# as14120_x31_adc.net
KiCad netlist of a schematic drawn in Altium Designer
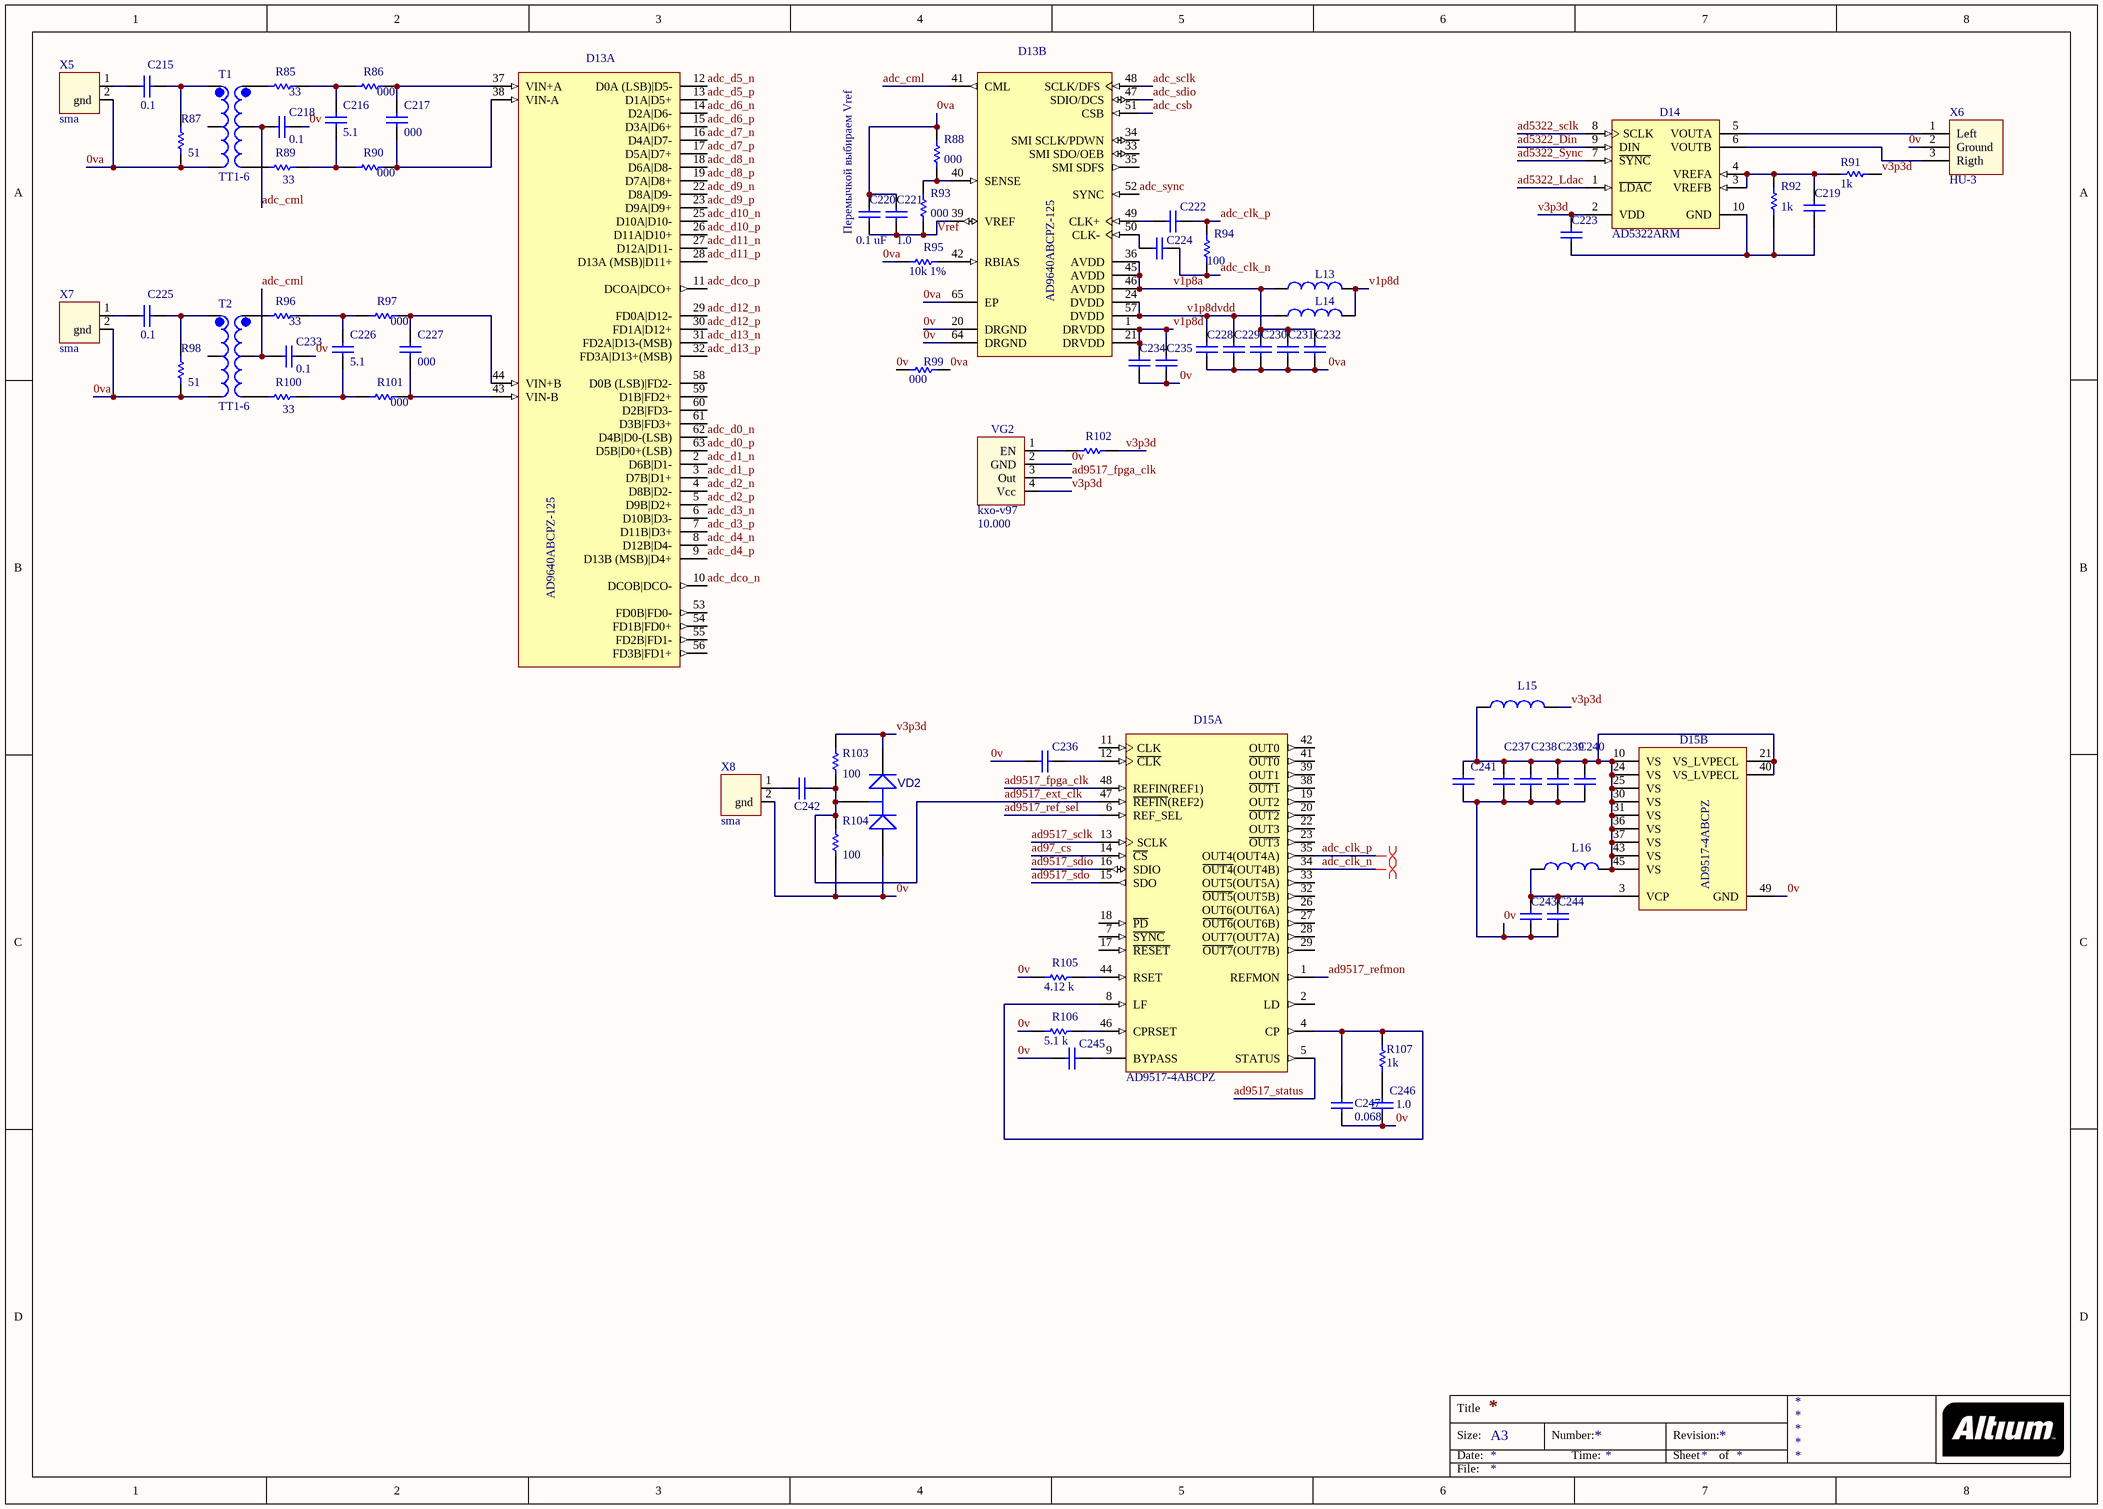
[diagram p0: as14120_x31_adc.SchDoc]

(export (version "E")
  (design (tool "Eeschema 10.0.6"))
  (components
    (comp (ref "C215")
      (value "0.1")
      (footprint "CAPC0402(1005)60_M")
      (description "CAP 1uF 10V ±20% 0402 (1005 Metric) Thickness 0.6mm SMD")
      (fields (field (name "TOLERANCE") "±20%") (field (name "Comment") "CAP 1uF 10V 0402(1005)"))
      (libsource (lib "as14120") (part "CAP_0402"))
    )
    (comp (ref "C216")
      (value "5.1")
      (footprint "CAPC0805(2012)100_N")
      (fields (field (name "Comment") "CAP_0805"))
      (libsource (lib "as14120") (part "CAP_0805"))
    )
    (comp (ref "C217")
      (value "000")
      (footprint "CAPC0805(2012)100_N")
      (fields (field (name "Comment") "CAP_0805"))
      (libsource (lib "as14120") (part "CAP_0805"))
    )
    (comp (ref "C218")
      (value "0.1")
      (footprint "CAPC0402(1005)60_M")
      (description "CAP 1uF 10V ±20% 0402 (1005 Metric) Thickness 0.6mm SMD")
      (fields (field (name "TOLERANCE") "±20%") (field (name "Comment") "CAP 1uF 10V 0402(1005)"))
      (libsource (lib "as14120") (part "CAP_0402"))
    )
    (comp (ref "C219")
      (value "CAP 1uF 10V 0402(1005)")
      (footprint "CAPC0402(1005)60_M")
      (description "CAP 1uF 10V ±20% 0402 (1005 Metric) Thickness 0.6mm SMD")
      (fields (field (name "TOLERANCE") "±20%"))
      (libsource (lib "as14120") (part "CAP_0402"))
    )
    (comp (ref "C220")
      (value "0.1 uF")
      (footprint "CAPC0402(1005)60_M")
      (description "CAP 1uF 10V ±20% 0402 (1005 Metric) Thickness 0.6mm SMD")
      (fields (field (name "TOLERANCE") "±20%") (field (name "Comment") "CAP 1uF 10V 0402(1005)"))
      (libsource (lib "as14120") (part "CAP_0402"))
    )
    (comp (ref "C221")
      (value "1.0")
      (footprint "CAPC0402(1005)60_M")
      (description "CAP 1uF 10V ±20% 0402 (1005 Metric) Thickness 0.6mm SMD")
      (fields (field (name "TOLERANCE") "±20%") (field (name "Comment") "CAP 1uF 10V 0402(1005)"))
      (libsource (lib "as14120") (part "CAP_0402"))
    )
    (comp (ref "C222")
      (value "CAP 1uF 10V 0402(1005)")
      (footprint "CAPC0402(1005)60_M")
      (description "CAP 1uF 10V ±20% 0402 (1005 Metric) Thickness 0.6mm SMD")
      (fields (field (name "TOLERANCE") "±20%"))
      (libsource (lib "as14120") (part "CAP_0402"))
    )
    (comp (ref "C223")
      (value "CAP 1uF 10V 0402(1005)")
      (footprint "CAPC0402(1005)60_M")
      (description "CAP 1uF 10V ±20% 0402 (1005 Metric) Thickness 0.6mm SMD")
      (fields (field (name "TOLERANCE") "±20%"))
      (libsource (lib "as14120") (part "CAP_0402"))
    )
    (comp (ref "C224")
      (value "CAP 1uF 10V 0402(1005)")
      (footprint "CAPC0402(1005)60_M")
      (description "CAP 1uF 10V ±20% 0402 (1005 Metric) Thickness 0.6mm SMD")
      (fields (field (name "TOLERANCE") "±20%"))
      (libsource (lib "as14120") (part "CAP_0402"))
    )
    (comp (ref "C225")
      (value "0.1")
      (footprint "CAPC0402(1005)60_M")
      (description "CAP 1uF 10V ±20% 0402 (1005 Metric) Thickness 0.6mm SMD")
      (fields (field (name "TOLERANCE") "±20%") (field (name "Comment") "CAP 1uF 10V 0402(1005)"))
      (libsource (lib "as14120") (part "CAP_0402"))
    )
    (comp (ref "C226")
      (value "5.1")
      (footprint "CAPC0805(2012)100_N")
      (fields (field (name "Comment") "CAP_0805"))
      (libsource (lib "as14120") (part "CAP_0805"))
    )
    (comp (ref "C227")
      (value "000")
      (footprint "CAPC0805(2012)100_N")
      (fields (field (name "Comment") "CAP_0805"))
      (libsource (lib "as14120") (part "CAP_0805"))
    )
    (comp (ref "C228")
      (value "CAP 1uF 10V 0402(1005)")
      (footprint "CAPC0402(1005)60_M")
      (description "CAP 1uF 10V ±20% 0402 (1005 Metric) Thickness 0.6mm SMD")
      (fields (field (name "TOLERANCE") "±20%"))
      (libsource (lib "as14120") (part "CAP_0402"))
    )
    (comp (ref "C229")
      (value "CAP 1uF 10V 0402(1005)")
      (footprint "CAPC0402(1005)60_M")
      (description "CAP 1uF 10V ±20% 0402 (1005 Metric) Thickness 0.6mm SMD")
      (fields (field (name "TOLERANCE") "±20%"))
      (libsource (lib "as14120") (part "CAP_0402"))
    )
    (comp (ref "C230")
      (value "CAP 1uF 10V 0402(1005)")
      (footprint "CAPC0402(1005)60_M")
      (description "CAP 1uF 10V ±20% 0402 (1005 Metric) Thickness 0.6mm SMD")
      (fields (field (name "TOLERANCE") "±20%"))
      (libsource (lib "as14120") (part "CAP_0402"))
    )
    (comp (ref "C231")
      (value "CAP 1uF 10V 0402(1005)")
      (footprint "CAPC0402(1005)60_M")
      (description "CAP 1uF 10V ±20% 0402 (1005 Metric) Thickness 0.6mm SMD")
      (fields (field (name "TOLERANCE") "±20%"))
      (libsource (lib "as14120") (part "CAP_0402"))
    )
    (comp (ref "C232")
      (value "CAP 1uF 10V 0402(1005)")
      (footprint "CAPC0402(1005)60_M")
      (description "CAP 1uF 10V ±20% 0402 (1005 Metric) Thickness 0.6mm SMD")
      (fields (field (name "TOLERANCE") "±20%"))
      (libsource (lib "as14120") (part "CAP_0402"))
    )
    (comp (ref "C233")
      (value "0.1")
      (footprint "CAPC0402(1005)60_M")
      (description "CAP 1uF 10V ±20% 0402 (1005 Metric) Thickness 0.6mm SMD")
      (fields (field (name "TOLERANCE") "±20%") (field (name "Comment") "CAP 1uF 10V 0402(1005)"))
      (libsource (lib "as14120") (part "CAP_0402"))
    )
    (comp (ref "C234")
      (value "CAP 1uF 10V 0402(1005)")
      (footprint "CAPC0402(1005)60_M")
      (description "CAP 1uF 10V ±20% 0402 (1005 Metric) Thickness 0.6mm SMD")
      (fields (field (name "TOLERANCE") "±20%"))
      (libsource (lib "as14120") (part "CAP_0402"))
    )
    (comp (ref "C235")
      (value "CAP 1uF 10V 0402(1005)")
      (footprint "CAPC0402(1005)60_M")
      (description "CAP 1uF 10V ±20% 0402 (1005 Metric) Thickness 0.6mm SMD")
      (fields (field (name "TOLERANCE") "±20%"))
      (libsource (lib "as14120") (part "CAP_0402"))
    )
    (comp (ref "C236")
      (value "CAP 1uF 10V 0402(1005)")
      (footprint "CAPC0402(1005)60_M")
      (description "CAP 1uF 10V ±20% 0402 (1005 Metric) Thickness 0.6mm SMD")
      (fields (field (name "TOLERANCE") "±20%"))
      (libsource (lib "as14120") (part "CAP_0402"))
    )
    (comp (ref "C237")
      (value "CAP 1uF 10V 0402(1005)")
      (footprint "CAPC0402(1005)60_M")
      (description "CAP 1uF 10V ±20% 0402 (1005 Metric) Thickness 0.6mm SMD")
      (fields (field (name "TOLERANCE") "±20%"))
      (libsource (lib "as14120") (part "CAP_0402"))
    )
    (comp (ref "C238")
      (value "CAP 1uF 10V 0402(1005)")
      (footprint "CAPC0402(1005)60_M")
      (description "CAP 1uF 10V ±20% 0402 (1005 Metric) Thickness 0.6mm SMD")
      (fields (field (name "TOLERANCE") "±20%"))
      (libsource (lib "as14120") (part "CAP_0402"))
    )
    (comp (ref "C239")
      (value "CAP 1uF 10V 0402(1005)")
      (footprint "CAPC0402(1005)60_M")
      (description "CAP 1uF 10V ±20% 0402 (1005 Metric) Thickness 0.6mm SMD")
      (fields (field (name "TOLERANCE") "±20%"))
      (libsource (lib "as14120") (part "CAP_0402"))
    )
    (comp (ref "C240")
      (value "CAP 1uF 10V 0402(1005)")
      (footprint "CAPC0402(1005)60_M")
      (description "CAP 1uF 10V ±20% 0402 (1005 Metric) Thickness 0.6mm SMD")
      (fields (field (name "TOLERANCE") "±20%"))
      (libsource (lib "as14120") (part "CAP_0402"))
    )
    (comp (ref "C241")
      (value "CAP 1uF 10V 0402(1005)")
      (footprint "CAPC0402(1005)60_M")
      (description "CAP 1uF 10V ±20% 0402 (1005 Metric) Thickness 0.6mm SMD")
      (fields (field (name "TOLERANCE") "±20%"))
      (libsource (lib "as14120") (part "CAP_0402"))
    )
    (comp (ref "C242")
      (value "CAP 1uF 10V 0402(1005)")
      (footprint "CAPC0402(1005)60_M")
      (description "CAP 1uF 10V ±20% 0402 (1005 Metric) Thickness 0.6mm SMD")
      (fields (field (name "TOLERANCE") "±20%"))
      (libsource (lib "as14120") (part "CAP_0402"))
    )
    (comp (ref "C243")
      (value "CAP 1uF 10V 0402(1005)")
      (footprint "CAPC0402(1005)60_M")
      (description "CAP 1uF 10V ±20% 0402 (1005 Metric) Thickness 0.6mm SMD")
      (fields (field (name "TOLERANCE") "±20%"))
      (libsource (lib "as14120") (part "CAP_0402"))
    )
    (comp (ref "C244")
      (value "CAP 1uF 10V 0402(1005)")
      (footprint "CAPC0402(1005)60_M")
      (description "CAP 1uF 10V ±20% 0402 (1005 Metric) Thickness 0.6mm SMD")
      (fields (field (name "TOLERANCE") "±20%"))
      (libsource (lib "as14120") (part "CAP_0402"))
    )
    (comp (ref "C245")
      (value "CAP 1uF 10V 0402(1005)")
      (footprint "CAPC0402(1005)60_M")
      (description "CAP 1uF 10V ±20% 0402 (1005 Metric) Thickness 0.6mm SMD")
      (fields (field (name "TOLERANCE") "±20%"))
      (libsource (lib "as14120") (part "CAP_0402"))
    )
    (comp (ref "C246")
      (value "1.0")
      (footprint "CAPC0805(2012)100_N")
      (fields (field (name "Comment") "CAP_0805"))
      (libsource (lib "as14120") (part "CAP_0805"))
    )
    (comp (ref "C247")
      (value "0.068")
      (footprint "CAPC0805(2012)100_N")
      (fields (field (name "Comment") "CAP_0805"))
      (libsource (lib "as14120") (part "CAP_0805"))
    )
    (comp (ref "D13")
      (value "AD9640ABCPZ-125")
      (footprint "CP-64-6_N")
      (fields (field (name "PART NUMBER") "AD9640-125") (field (name "MANUFACTURER") "Analog Devices"))
      (libsource (lib "Analog Devices Data Converters Analog-to-Digital Converters") (part "AD9640ABCPZ-125"))
    )
    (comp (ref "D14")
      (value "AD5322ARM")
      (footprint "RM-10_L")
      (fields (field (name "ADI PART NUMBER") "AD5322") (field (name "MANUFACTURER") "Analog Devices"))
      (libsource (lib "Analog Devices Data Converters Digital-to-Analog Converters") (part "AD5322ARM"))
    )
    (comp (ref "D15")
      (value "AD9517-4ABCPZ")
      (footprint "ADI-CP-48-8_L")
      (libsource (lib "Analog Devices RF IF Timing ICs and Clocks") (part "AD9517-4ABCPZ"))
    )
    (comp (ref "L13")
      (value "BLM21PG300SN1D")
      (footprint "CAPC0805(2012)100_N")
      (libsource (lib "as14120") (part "Ferrite_beat"))
    )
    (comp (ref "L14")
      (value "BLM21PG300SN1D")
      (footprint "CAPC0805(2012)100_N")
      (libsource (lib "as14120") (part "Ferrite_beat"))
    )
    (comp (ref "L15")
      (value "BLM21PG300SN1D")
      (footprint "CAPC0805(2012)100_N")
      (libsource (lib "as14120") (part "Ferrite_beat"))
    )
    (comp (ref "L16")
      (value "BLM21PG300SN1D")
      (footprint "CAPC0805(2012)100_N")
      (libsource (lib "as14120") (part "Ferrite_beat"))
    )
    (comp (ref "R85")
      (value "33")
      (footprint "RESC0805(2012)_L")
      (description "1K 0.125W 1% 0805 (2012 Metric)  SMD")
      (fields (field (name "TOLERANCE") "1 %") (field (name "POWER") "0.125 W"))
      (libsource (lib "as14120") (part "RES_0805"))
    )
    (comp (ref "R86")
      (value "000")
      (footprint "RESC0805(2012)_L")
      (description "1K 0.125W 1% 0805 (2012 Metric)  SMD")
      (fields (field (name "TOLERANCE") "1 %") (field (name "POWER") "0.125 W"))
      (libsource (lib "as14120") (part "RES_0805"))
    )
    (comp (ref "R87")
      (value "51")
      (footprint "RESC0805(2012)_L")
      (description "1K 0.125W 1% 0805 (2012 Metric)  SMD")
      (fields (field (name "TOLERANCE") "1 %") (field (name "POWER") "0.125 W"))
      (libsource (lib "as14120") (part "RES_0805"))
    )
    (comp (ref "R88")
      (value "000")
      (footprint "RESC0603(1608)_L")
      (description "1K 0.1W 5% 0603 (1608 Metric)  SMD")
      (fields (field (name "TOLERANCE") "5 %") (field (name "POWER") "0.1 W"))
      (libsource (lib "as14120") (part "RES_0603"))
    )
    (comp (ref "R89")
      (value "33")
      (footprint "RESC0805(2012)_L")
      (description "1K 0.125W 1% 0805 (2012 Metric)  SMD")
      (fields (field (name "TOLERANCE") "1 %") (field (name "POWER") "0.125 W"))
      (libsource (lib "as14120") (part "RES_0805"))
    )
    (comp (ref "R90")
      (value "000")
      (footprint "RESC0805(2012)_L")
      (description "1K 0.125W 1% 0805 (2012 Metric)  SMD")
      (fields (field (name "TOLERANCE") "1 %") (field (name "POWER") "0.125 W"))
      (libsource (lib "as14120") (part "RES_0805"))
    )
    (comp (ref "R91")
      (value "1k")
      (footprint "RESC0603(1608)_L")
      (description "1K 0.1W 5% 0603 (1608 Metric)  SMD")
      (fields (field (name "TOLERANCE") "5 %") (field (name "POWER") "0.1 W"))
      (libsource (lib "as14120") (part "RES_0603"))
    )
    (comp (ref "R92")
      (value "1k")
      (footprint "RESC0603(1608)_L")
      (description "1K 0.1W 5% 0603 (1608 Metric)  SMD")
      (fields (field (name "TOLERANCE") "5 %") (field (name "POWER") "0.1 W"))
      (libsource (lib "as14120") (part "RES_0603"))
    )
    (comp (ref "R93")
      (value "000")
      (footprint "RESC0603(1608)_L")
      (description "1K 0.1W 5% 0603 (1608 Metric)  SMD")
      (fields (field (name "TOLERANCE") "5 %") (field (name "POWER") "0.1 W"))
      (libsource (lib "as14120") (part "RES_0603"))
    )
    (comp (ref "R94")
      (value "100")
      (footprint "RESC0805(2012)_L")
      (description "1K 0.125W 1% 0805 (2012 Metric)  SMD")
      (fields (field (name "TOLERANCE") "1 %") (field (name "POWER") "0.125 W"))
      (libsource (lib "as14120") (part "RES_0805"))
    )
    (comp (ref "R95")
      (value "10k 1%")
      (footprint "RESC0805(2012)_L")
      (description "1K 0.125W 1% 0805 (2012 Metric)  SMD")
      (fields (field (name "TOLERANCE") "1 %") (field (name "POWER") "0.125 W"))
      (libsource (lib "as14120") (part "RES_0805"))
    )
    (comp (ref "R96")
      (value "33")
      (footprint "RESC0805(2012)_L")
      (description "1K 0.125W 1% 0805 (2012 Metric)  SMD")
      (fields (field (name "TOLERANCE") "1 %") (field (name "POWER") "0.125 W"))
      (libsource (lib "as14120") (part "RES_0805"))
    )
    (comp (ref "R97")
      (value "000")
      (footprint "RESC0805(2012)_L")
      (description "1K 0.125W 1% 0805 (2012 Metric)  SMD")
      (fields (field (name "TOLERANCE") "1 %") (field (name "POWER") "0.125 W"))
      (libsource (lib "as14120") (part "RES_0805"))
    )
    (comp (ref "R98")
      (value "51")
      (footprint "RESC0805(2012)_L")
      (description "1K 0.125W 1% 0805 (2012 Metric)  SMD")
      (fields (field (name "TOLERANCE") "1 %") (field (name "POWER") "0.125 W"))
      (libsource (lib "as14120") (part "RES_0805"))
    )
    (comp (ref "R99")
      (value "000")
      (footprint "RESC0603(1608)_L")
      (description "1K 0.1W 5% 0603 (1608 Metric)  SMD")
      (fields (field (name "TOLERANCE") "5 %") (field (name "POWER") "0.1 W"))
      (libsource (lib "as14120") (part "RES_0603"))
    )
    (comp (ref "R100")
      (value "33")
      (footprint "RESC0805(2012)_L")
      (description "1K 0.125W 1% 0805 (2012 Metric)  SMD")
      (fields (field (name "TOLERANCE") "1 %") (field (name "POWER") "0.125 W"))
      (libsource (lib "as14120") (part "RES_0805"))
    )
    (comp (ref "R101")
      (value "000")
      (footprint "RESC0805(2012)_L")
      (description "1K 0.125W 1% 0805 (2012 Metric)  SMD")
      (fields (field (name "TOLERANCE") "1 %") (field (name "POWER") "0.125 W"))
      (libsource (lib "as14120") (part "RES_0805"))
    )
    (comp (ref "R102")
      (value "1K 5% 0603(1608)")
      (footprint "RESC0603(1608)_L")
      (description "1K 0.1W 5% 0603 (1608 Metric)  SMD")
      (fields (field (name "TOLERANCE") "5 %") (field (name "POWER") "0.1 W"))
      (libsource (lib "as14120") (part "RES_0603"))
    )
    (comp (ref "R103")
      (value "100")
      (footprint "RESC0805(2012)_L")
      (description "1K 0.125W 1% 0805 (2012 Metric)  SMD")
      (fields (field (name "TOLERANCE") "1 %") (field (name "POWER") "0.125 W"))
      (libsource (lib "as14120") (part "RES_0805"))
    )
    (comp (ref "R104")
      (value "100")
      (footprint "RESC0805(2012)_L")
      (description "1K 0.125W 1% 0805 (2012 Metric)  SMD")
      (fields (field (name "TOLERANCE") "1 %") (field (name "POWER") "0.125 W"))
      (libsource (lib "as14120") (part "RES_0805"))
    )
    (comp (ref "R105")
      (value "4.12 k")
      (footprint "RESC0805(2012)_L")
      (description "1K 0.125W 1% 0805 (2012 Metric)  SMD")
      (fields (field (name "TOLERANCE") "1 %") (field (name "POWER") "0.125 W"))
      (libsource (lib "as14120") (part "RES_0805"))
    )
    (comp (ref "R106")
      (value "5.1 k")
      (footprint "RESC0805(2012)_L")
      (description "1K 0.125W 1% 0805 (2012 Metric)  SMD")
      (fields (field (name "TOLERANCE") "1 %") (field (name "POWER") "0.125 W"))
      (libsource (lib "as14120") (part "RES_0805"))
    )
    (comp (ref "R107")
      (value "1k")
      (footprint "RESC0805(2012)_L")
      (description "1K 0.125W 1% 0805 (2012 Metric)  SMD")
      (fields (field (name "TOLERANCE") "1 %") (field (name "POWER") "0.125 W"))
      (libsource (lib "as14120") (part "RES_0805"))
    )
    (comp (ref "T1") (value "TT1-6") (footprint "TT!-6-KK81") (libsource (lib "as14120") (part "TT1-6-KK81")))
    (comp (ref "T2") (value "TT1-6") (footprint "TT!-6-KK81") (libsource (lib "as14120") (part "TT1-6-KK81")))
    (comp (ref "VD2")
      (value "BAV99")
      (footprint "SO-G3/X.9")
      (description "SOT23 Silicon Planar High-Speed Switching Series Diode Pair")
      (libsource (lib "alexsb") (part "BAV99"))
    )
    (comp (ref "VG2")
      (value "kxo-v97")
      (footprint "kxo-v97")
      (fields (field (name "ALTIUM_VALUE") "10.000"))
      (libsource (lib "as14120") (part "kxo-v97"))
    )
    (comp (ref "X5") (value "sma") (footprint "sma") (libsource (lib "as14120") (part "sma")))
    (comp (ref "X6") (value "HU-3") (footprint "HU-3") (libsource (lib "as14120") (part "HU-3")))
    (comp (ref "X7") (value "sma") (footprint "sma") (libsource (lib "as14120") (part "sma")))
    (comp (ref "X8") (value "sma") (footprint "sma") (libsource (lib "as14120") (part "sma")))
  )
  (nets
    (net (code "1") (name "/0v") (class "Default")
      (node (ref "C218") (pin "2") (pinfunction "2_2") (pintype "passive"))
      (node (ref "C233") (pin "2") (pinfunction "2_2") (pintype "passive"))
      (node (ref "C234") (pin "1") (pinfunction "1_1") (pintype "passive"))
      (node (ref "C235") (pin "1") (pinfunction "1_1") (pintype "passive"))
      (node (ref "C236") (pin "1") (pinfunction "1_1") (pintype "passive"))
      (node (ref "C237") (pin "1") (pinfunction "1_1") (pintype "passive"))
      (node (ref "C238") (pin "1") (pinfunction "1_1") (pintype "passive"))
      (node (ref "C239") (pin "1") (pinfunction "1_1") (pintype "passive"))
      (node (ref "C240") (pin "1") (pinfunction "1_1") (pintype "passive"))
      (node (ref "C241") (pin "1") (pinfunction "1_1") (pintype "passive"))
      (node (ref "C243") (pin "1") (pinfunction "1_1") (pintype "passive"))
      (node (ref "C244") (pin "1") (pinfunction "1_1") (pintype "passive"))
      (node (ref "C245") (pin "1") (pinfunction "1_1") (pintype "passive"))
      (node (ref "C246") (pin "1") (pinfunction "1_1") (pintype "passive"))
      (node (ref "C247") (pin "1") (pinfunction "1_1") (pintype "passive"))
      (node (ref "D13") (pin "20") (pinfunction "DRGND_20") (pintype "power_in"))
      (node (ref "D13") (pin "64") (pinfunction "DRGND_64") (pintype "power_in"))
      (node (ref "D15") (pin "49") (pinfunction "GND_49") (pintype "power_in"))
      (node (ref "R104") (pin "1") (pinfunction "1_1") (pintype "passive"))
      (node (ref "R105") (pin "2") (pinfunction "2_2") (pintype "passive"))
      (node (ref "R106") (pin "2") (pinfunction "2_2") (pintype "passive"))
      (node (ref "R99") (pin "1") (pinfunction "1_1") (pintype "passive"))
      (node (ref "VD2") (pin "3") (pinfunction "A_3") (pintype "passive"))
      (node (ref "VG2") (pin "2") (pinfunction "GND_2") (pintype "passive"))
      (node (ref "X6") (pin "2") (pinfunction "Ground_2") (pintype "passive"))
      (node (ref "X8") (pin "2") (pinfunction "gnd_2") (pintype "passive"))
    )
    (net (code "2") (name "/0va") (class "Default")
      (node (ref "C220") (pin "2") (pinfunction "2_2") (pintype "passive"))
      (node (ref "C221") (pin "2") (pinfunction "2_2") (pintype "passive"))
      (node (ref "C228") (pin "1") (pinfunction "1_1") (pintype "passive"))
      (node (ref "C229") (pin "1") (pinfunction "1_1") (pintype "passive"))
      (node (ref "C230") (pin "1") (pinfunction "1_1") (pintype "passive"))
      (node (ref "C231") (pin "1") (pinfunction "1_1") (pintype "passive"))
      (node (ref "C232") (pin "1") (pinfunction "1_1") (pintype "passive"))
      (node (ref "D13") (pin "65") (pinfunction "EP_65") (pintype "power_in"))
      (node (ref "R87") (pin "1") (pinfunction "1_1") (pintype "passive"))
      (node (ref "R88") (pin "1") (pinfunction "1_1") (pintype "passive"))
      (node (ref "R95") (pin "2") (pinfunction "2_2") (pintype "passive"))
      (node (ref "R98") (pin "1") (pinfunction "1_1") (pintype "passive"))
      (node (ref "R99") (pin "2") (pinfunction "2_2") (pintype "passive"))
      (node (ref "T1") (pin "6") (pinfunction "6_6") (pintype "passive"))
      (node (ref "T2") (pin "6") (pinfunction "6_6") (pintype "passive"))
      (node (ref "X5") (pin "2") (pinfunction "gnd_2") (pintype "passive"))
      (node (ref "X7") (pin "2") (pinfunction "gnd_2") (pintype "passive"))
    )
    (net (code "3") (name "/Vref") (class "Default")
      (node (ref "C220") (pin "1") (pinfunction "1_1") (pintype "passive"))
      (node (ref "C221") (pin "1") (pinfunction "1_1") (pintype "passive"))
      (node (ref "D13") (pin "39") (pinfunction "VREF_39") (pintype "bidirectional"))
      (node (ref "R93") (pin "2") (pinfunction "2_2") (pintype "passive"))
    )
    (net (code "4") (name "/ad97_cs") (class "Default")
      (node (ref "D15") (pin "14") (pinfunction "~{CS}_14") (pintype "input"))
    )
    (net (code "5") (name "/ad5322_Din") (class "Default")
      (node (ref "D14") (pin "9") (pinfunction "DIN_9") (pintype "input"))
    )
    (net (code "6") (name "/ad5322_Ldac") (class "Default")
      (node (ref "D14") (pin "1") (pinfunction "~{LDAC}_1") (pintype "input"))
    )
    (net (code "7") (name "/ad5322_Sync") (class "Default")
      (node (ref "D14") (pin "7") (pinfunction "~{SYNC}_7") (pintype "input"))
    )
    (net (code "8") (name "/ad5322_sclk") (class "Default")
      (node (ref "D14") (pin "8") (pinfunction "SCLK_8") (pintype "input"))
    )
    (net (code "9") (name "/ad9517_ext_clk") (class "Default")
      (node (ref "C242") (pin "2") (pinfunction "2_2") (pintype "passive"))
      (node (ref "D15") (pin "47") (pinfunction "~{REFIN}(REF2)_47") (pintype "input"))
      (node (ref "R103") (pin "1") (pinfunction "1_1") (pintype "passive"))
      (node (ref "R104") (pin "2") (pinfunction "2_2") (pintype "passive"))
      (node (ref "VD2") (pin "1") (pinfunction "C_1") (pintype "passive"))
    )
    (net (code "10") (name "/ad9517_fpga_clk") (class "Default")
      (node (ref "D15") (pin "48") (pinfunction "REFIN(REF1)_48") (pintype "input"))
      (node (ref "VG2") (pin "3") (pinfunction "Out_3") (pintype "passive"))
    )
    (net (code "11") (name "/ad9517_ref_sel") (class "Default")
      (node (ref "D15") (pin "6") (pinfunction "REF_SEL_6") (pintype "input"))
    )
    (net (code "12") (name "/ad9517_refmon") (class "Default")
      (node (ref "D15") (pin "1") (pinfunction "REFMON_1") (pintype "output"))
    )
    (net (code "13") (name "/ad9517_sclk") (class "Default")
      (node (ref "D15") (pin "13") (pinfunction "SCLK_13") (pintype "input"))
    )
    (net (code "14") (name "/ad9517_sdio") (class "Default")
      (node (ref "D15") (pin "16") (pinfunction "SDIO_16") (pintype "bidirectional"))
    )
    (net (code "15") (name "/ad9517_sdo") (class "Default")
      (node (ref "D15") (pin "15") (pinfunction "SDO_15") (pintype "output"))
    )
    (net (code "16") (name "/ad9517_status") (class "Default")
      (node (ref "D15") (pin "5") (pinfunction "STATUS_5") (pintype "output"))
    )
    (net (code "17") (name "/adc_clk_n") (class "Default")
      (node (ref "C224") (pin "1") (pinfunction "1_1") (pintype "passive"))
      (node (ref "D15") (pin "34") (pinfunction "~{OUT4}(OUT4B)_34") (pintype "output"))
      (node (ref "R94") (pin "1") (pinfunction "1_1") (pintype "passive"))
    )
    (net (code "18") (name "/adc_clk_p") (class "Default")
      (node (ref "C222") (pin "1") (pinfunction "1_1") (pintype "passive"))
      (node (ref "D15") (pin "35") (pinfunction "OUT4(OUT4A)_35") (pintype "output"))
      (node (ref "R94") (pin "2") (pinfunction "2_2") (pintype "passive"))
    )
    (net (code "19") (name "/adc_cml") (class "Default")
      (node (ref "C218") (pin "1") (pinfunction "1_1") (pintype "passive"))
      (node (ref "C233") (pin "1") (pinfunction "1_1") (pintype "passive"))
      (node (ref "D13") (pin "41") (pinfunction "CML_41") (pintype "output"))
      (node (ref "T1") (pin "2") (pinfunction "2_2") (pintype "passive"))
      (node (ref "T2") (pin "2") (pinfunction "2_2") (pintype "passive"))
    )
    (net (code "20") (name "/adc_csb") (class "Default")
      (node (ref "D13") (pin "51") (pinfunction "CSB_51") (pintype "input"))
    )
    (net (code "21") (name "/adc_d0_n") (class "Default")
      (node (ref "D13") (pin "62") (pinfunction "D4BD0-(LSB)_62") (pintype "tri_state"))
    )
    (net (code "22") (name "/adc_d0_p") (class "Default")
      (node (ref "D13") (pin "63") (pinfunction "D5BD0+(LSB)_63") (pintype "tri_state"))
    )
    (net (code "23") (name "/adc_d1_n") (class "Default")
      (node (ref "D13") (pin "2") (pinfunction "D6BD1-_2") (pintype "tri_state"))
    )
    (net (code "24") (name "/adc_d1_p") (class "Default")
      (node (ref "D13") (pin "3") (pinfunction "D7BD1+_3") (pintype "tri_state"))
    )
    (net (code "25") (name "/adc_d2_n") (class "Default")
      (node (ref "D13") (pin "4") (pinfunction "D8BD2-_4") (pintype "tri_state"))
    )
    (net (code "26") (name "/adc_d2_p") (class "Default")
      (node (ref "D13") (pin "5") (pinfunction "D9BD2+_5") (pintype "tri_state"))
    )
    (net (code "27") (name "/adc_d3_n") (class "Default")
      (node (ref "D13") (pin "6") (pinfunction "D10BD3-_6") (pintype "tri_state"))
    )
    (net (code "28") (name "/adc_d3_p") (class "Default")
      (node (ref "D13") (pin "7") (pinfunction "D11BD3+_7") (pintype "tri_state"))
    )
    (net (code "29") (name "/adc_d4_n") (class "Default")
      (node (ref "D13") (pin "8") (pinfunction "D12BD4-_8") (pintype "tri_state"))
    )
    (net (code "30") (name "/adc_d4_p") (class "Default")
      (node (ref "D13") (pin "9") (pinfunction "D13B_(MSB)D4+_9") (pintype "tri_state"))
    )
    (net (code "31") (name "/adc_d5_n") (class "Default")
      (node (ref "D13") (pin "12") (pinfunction "D0A_(LSB)D5-_12") (pintype "tri_state"))
    )
    (net (code "32") (name "/adc_d5_p") (class "Default")
      (node (ref "D13") (pin "13") (pinfunction "D1AD5+_13") (pintype "tri_state"))
    )
    (net (code "33") (name "/adc_d6_n") (class "Default")
      (node (ref "D13") (pin "14") (pinfunction "D2AD6-_14") (pintype "tri_state"))
    )
    (net (code "34") (name "/adc_d6_p") (class "Default")
      (node (ref "D13") (pin "15") (pinfunction "D3AD6+_15") (pintype "tri_state"))
    )
    (net (code "35") (name "/adc_d7_n") (class "Default")
      (node (ref "D13") (pin "16") (pinfunction "D4AD7-_16") (pintype "tri_state"))
    )
    (net (code "36") (name "/adc_d7_p") (class "Default")
      (node (ref "D13") (pin "17") (pinfunction "D5AD7+_17") (pintype "tri_state"))
    )
    (net (code "37") (name "/adc_d8_n") (class "Default")
      (node (ref "D13") (pin "18") (pinfunction "D6AD8-_18") (pintype "tri_state"))
    )
    (net (code "38") (name "/adc_d8_p") (class "Default")
      (node (ref "D13") (pin "19") (pinfunction "D7AD8+_19") (pintype "tri_state"))
    )
    (net (code "39") (name "/adc_d9_n") (class "Default")
      (node (ref "D13") (pin "22") (pinfunction "D8AD9-_22") (pintype "tri_state"))
    )
    (net (code "40") (name "/adc_d9_p") (class "Default")
      (node (ref "D13") (pin "23") (pinfunction "D9AD9+_23") (pintype "tri_state"))
    )
    (net (code "41") (name "/adc_d10_n") (class "Default")
      (node (ref "D13") (pin "25") (pinfunction "D10AD10-_25") (pintype "tri_state"))
    )
    (net (code "42") (name "/adc_d10_p") (class "Default")
      (node (ref "D13") (pin "26") (pinfunction "D11AD10+_26") (pintype "tri_state"))
    )
    (net (code "43") (name "/adc_d11_n") (class "Default")
      (node (ref "D13") (pin "27") (pinfunction "D12AD11-_27") (pintype "tri_state"))
    )
    (net (code "44") (name "/adc_d11_p") (class "Default")
      (node (ref "D13") (pin "28") (pinfunction "D13A_(MSB)D11+_28") (pintype "tri_state"))
    )
    (net (code "45") (name "/adc_d12_n") (class "Default")
      (node (ref "D13") (pin "29") (pinfunction "FD0AD12-_29") (pintype "tri_state"))
    )
    (net (code "46") (name "/adc_d12_p") (class "Default")
      (node (ref "D13") (pin "30") (pinfunction "FD1AD12+_30") (pintype "tri_state"))
    )
    (net (code "47") (name "/adc_d13_n") (class "Default")
      (node (ref "D13") (pin "31") (pinfunction "FD2AD13-(MSB)_31") (pintype "tri_state"))
    )
    (net (code "48") (name "/adc_d13_p") (class "Default")
      (node (ref "D13") (pin "32") (pinfunction "FD3AD13+(MSB)_32") (pintype "tri_state"))
    )
    (net (code "49") (name "/adc_dco_n") (class "Default")
      (node (ref "D13") (pin "10") (pinfunction "DCOBDCO-_10") (pintype "output"))
    )
    (net (code "50") (name "/adc_dco_p") (class "Default")
      (node (ref "D13") (pin "11") (pinfunction "DCOADCO+_11") (pintype "output"))
    )
    (net (code "51") (name "/adc_sclk") (class "Default")
      (node (ref "D13") (pin "48") (pinfunction "SCLK/DFS_48") (pintype "input"))
    )
    (net (code "52") (name "/adc_sdio") (class "Default")
      (node (ref "D13") (pin "47") (pinfunction "SDIO/DCS_47") (pintype "bidirectional"))
    )
    (net (code "53") (name "/adc_sync") (class "Default")
      (node (ref "D13") (pin "52") (pinfunction "SYNC_52") (pintype "input"))
    )
    (net (code "54") (name "/v1p8a") (class "Default")
      (node (ref "C230") (pin "2") (pinfunction "2_2") (pintype "passive"))
      (node (ref "C231") (pin "2") (pinfunction "2_2") (pintype "passive"))
      (node (ref "C232") (pin "2") (pinfunction "2_2") (pintype "passive"))
      (node (ref "D13") (pin "36") (pinfunction "AVDD_36") (pintype "power_in"))
      (node (ref "D13") (pin "45") (pinfunction "AVDD_45") (pintype "power_in"))
      (node (ref "D13") (pin "46") (pinfunction "AVDD_46") (pintype "power_in"))
      (node (ref "L13") (pin "1") (pinfunction "1_1") (pintype "passive"))
    )
    (net (code "55") (name "/v1p8d") (class "Default")
      (node (ref "C234") (pin "2") (pinfunction "2_2") (pintype "passive"))
      (node (ref "C235") (pin "2") (pinfunction "2_2") (pintype "passive"))
      (node (ref "D13") (pin "1") (pinfunction "DRVDD_1") (pintype "power_in"))
      (node (ref "D13") (pin "21") (pinfunction "DRVDD_21") (pintype "power_in"))
      (node (ref "L13") (pin "2") (pinfunction "2_2") (pintype "passive"))
      (node (ref "L14") (pin "2") (pinfunction "2_2") (pintype "passive"))
    )
    (net (code "56") (name "/v1p8dvdd") (class "Default")
      (node (ref "C228") (pin "2") (pinfunction "2_2") (pintype "passive"))
      (node (ref "C229") (pin "2") (pinfunction "2_2") (pintype "passive"))
      (node (ref "D13") (pin "24") (pinfunction "DVDD_24") (pintype "power_in"))
      (node (ref "D13") (pin "57") (pinfunction "DVDD_57") (pintype "power_in"))
      (node (ref "L14") (pin "1") (pinfunction "1_1") (pintype "passive"))
    )
    (net (code "57") (name "/v3p3d") (class "Default")
      (node (ref "C223") (pin "2") (pinfunction "2_2") (pintype "passive"))
      (node (ref "D14") (pin "2") (pinfunction "VDD_2") (pintype "power_in"))
      (node (ref "L15") (pin "2") (pinfunction "2_2") (pintype "passive"))
      (node (ref "R102") (pin "1") (pinfunction "1_1") (pintype "passive"))
      (node (ref "R103") (pin "2") (pinfunction "2_2") (pintype "passive"))
      (node (ref "R91") (pin "2") (pinfunction "2_2") (pintype "passive"))
      (node (ref "VD2") (pin "2") (pinfunction "K_2") (pintype "passive"))
      (node (ref "VG2") (pin "4") (pinfunction "Vcc_4") (pintype "passive"))
    )
    (net (code "58") (name "Net-(C215-Pad1)") (class "Default")
      (node (ref "C215") (pin "1") (pinfunction "1_1") (pintype "passive"))
      (node (ref "X5") (pin "1") (pintype "passive"))
    )
    (net (code "59") (name "Net-(C215-Pad2)") (class "Default")
      (node (ref "C215") (pin "2") (pinfunction "2_2") (pintype "passive"))
      (node (ref "R87") (pin "2") (pinfunction "2_2") (pintype "passive"))
      (node (ref "T1") (pin "4") (pinfunction "4_4") (pintype "passive"))
    )
    (net (code "60") (name "Net-(C216-Pad1)") (class "Default")
      (node (ref "C216") (pin "1") (pinfunction "1_1") (pintype "passive"))
      (node (ref "R89") (pin "1") (pinfunction "1_1") (pintype "passive"))
      (node (ref "R90") (pin "2") (pinfunction "2_2") (pintype "passive"))
    )
    (net (code "61") (name "Net-(C216-Pad2)") (class "Default")
      (node (ref "C216") (pin "2") (pinfunction "2_2") (pintype "passive"))
      (node (ref "R85") (pin "1") (pinfunction "1_1") (pintype "passive"))
      (node (ref "R86") (pin "2") (pinfunction "2_2") (pintype "passive"))
    )
    (net (code "62") (name "Net-(C225-Pad1)") (class "Default")
      (node (ref "C225") (pin "1") (pinfunction "1_1") (pintype "passive"))
      (node (ref "X7") (pin "1") (pintype "passive"))
    )
    (net (code "63") (name "Net-(C225-Pad2)") (class "Default")
      (node (ref "C225") (pin "2") (pinfunction "2_2") (pintype "passive"))
      (node (ref "R98") (pin "2") (pinfunction "2_2") (pintype "passive"))
      (node (ref "T2") (pin "4") (pinfunction "4_4") (pintype "passive"))
    )
    (net (code "64") (name "Net-(C226-Pad1)") (class "Default")
      (node (ref "C226") (pin "1") (pinfunction "1_1") (pintype "passive"))
      (node (ref "R100") (pin "1") (pinfunction "1_1") (pintype "passive"))
      (node (ref "R101") (pin "2") (pinfunction "2_2") (pintype "passive"))
    )
    (net (code "65") (name "Net-(C226-Pad2)") (class "Default")
      (node (ref "C226") (pin "2") (pinfunction "2_2") (pintype "passive"))
      (node (ref "R96") (pin "1") (pinfunction "1_1") (pintype "passive"))
      (node (ref "R97") (pin "2") (pinfunction "2_2") (pintype "passive"))
    )
    (net (code "66") (name "Net-(C237-Pad2)") (class "Default")
      (node (ref "C237") (pin "2") (pinfunction "2_2") (pintype "passive"))
      (node (ref "C238") (pin "2") (pinfunction "2_2") (pintype "passive"))
      (node (ref "C239") (pin "2") (pinfunction "2_2") (pintype "passive"))
      (node (ref "C240") (pin "2") (pinfunction "2_2") (pintype "passive"))
      (node (ref "C241") (pin "2") (pinfunction "2_2") (pintype "passive"))
      (node (ref "D15") (pin "10") (pinfunction "VS_10") (pintype "power_in"))
      (node (ref "D15") (pin "21") (pinfunction "VS_LVPECL_21") (pintype "power_in"))
      (node (ref "D15") (pin "24") (pinfunction "VS_24") (pintype "power_in"))
      (node (ref "D15") (pin "25") (pinfunction "VS_25") (pintype "power_in"))
      (node (ref "D15") (pin "30") (pinfunction "VS_30") (pintype "power_in"))
      (node (ref "D15") (pin "31") (pinfunction "VS_31") (pintype "power_in"))
      (node (ref "D15") (pin "36") (pinfunction "VS_36") (pintype "power_in"))
      (node (ref "D15") (pin "37") (pinfunction "VS_37") (pintype "power_in"))
      (node (ref "D15") (pin "40") (pinfunction "VS_LVPECL_40") (pintype "power_in"))
      (node (ref "D15") (pin "43") (pinfunction "VS_43") (pintype "power_in"))
      (node (ref "D15") (pin "45") (pinfunction "VS_45") (pintype "power_in"))
      (node (ref "L15") (pin "1") (pinfunction "1_1") (pintype "passive"))
      (node (ref "L16") (pin "2") (pinfunction "2_2") (pintype "passive"))
    )
    (net (code "67") (name "Net-(C242-Pad1)") (class "Default")
      (node (ref "C242") (pin "1") (pinfunction "1_1") (pintype "passive"))
      (node (ref "X8") (pin "1") (pintype "passive"))
    )
    (net (code "68") (name "Net-(C246-Pad2)") (class "Default")
      (node (ref "C246") (pin "2") (pinfunction "2_2") (pintype "passive"))
      (node (ref "R107") (pin "2") (pinfunction "2_2") (pintype "passive"))
    )
    (net (code "69") (name "Net-(D13A-VIN+A)") (class "Default")
      (node (ref "C217") (pin "2") (pinfunction "2_2") (pintype "passive"))
      (node (ref "D13") (pin "37") (pinfunction "VIN+A_37") (pintype "input"))
      (node (ref "R86") (pin "1") (pinfunction "1_1") (pintype "passive"))
    )
    (net (code "70") (name "Net-(D13A-VIN+B)") (class "Default")
      (node (ref "C227") (pin "2") (pinfunction "2_2") (pintype "passive"))
      (node (ref "D13") (pin "44") (pinfunction "VIN+B_44") (pintype "input"))
      (node (ref "R97") (pin "1") (pinfunction "1_1") (pintype "passive"))
    )
    (net (code "71") (name "Net-(D13A-VIN-A)") (class "Default")
      (node (ref "C217") (pin "1") (pinfunction "1_1") (pintype "passive"))
      (node (ref "D13") (pin "38") (pinfunction "VIN-A_38") (pintype "input"))
      (node (ref "R90") (pin "1") (pinfunction "1_1") (pintype "passive"))
    )
    (net (code "72") (name "Net-(D13A-VIN-B)") (class "Default")
      (node (ref "C227") (pin "1") (pinfunction "1_1") (pintype "passive"))
      (node (ref "D13") (pin "43") (pinfunction "VIN-B_43") (pintype "input"))
      (node (ref "R101") (pin "1") (pinfunction "1_1") (pintype "passive"))
    )
    (net (code "73") (name "Net-(D13B-CLK+)") (class "Default")
      (node (ref "C222") (pin "2") (pinfunction "2_2") (pintype "passive"))
      (node (ref "D13") (pin "49") (pinfunction "CLK+_49") (pintype "input"))
    )
    (net (code "74") (name "Net-(D13B-CLK-)") (class "Default")
      (node (ref "C224") (pin "2") (pinfunction "2_2") (pintype "passive"))
      (node (ref "D13") (pin "50") (pinfunction "CLK-_50") (pintype "input"))
    )
    (net (code "75") (name "Net-(D13B-RBIAS)") (class "Default")
      (node (ref "D13") (pin "42") (pinfunction "RBIAS_42") (pintype "input"))
      (node (ref "R95") (pin "1") (pinfunction "1_1") (pintype "passive"))
    )
    (net (code "76") (name "Net-(D13B-SENSE)") (class "Default")
      (node (ref "D13") (pin "40") (pinfunction "SENSE_40") (pintype "input"))
      (node (ref "R88") (pin "2") (pinfunction "2_2") (pintype "passive"))
      (node (ref "R93") (pin "1") (pinfunction "1_1") (pintype "passive"))
    )
    (net (code "77") (name "Net-(D14-GND)") (class "Default")
      (node (ref "C219") (pin "1") (pinfunction "1_1") (pintype "passive"))
      (node (ref "C223") (pin "1") (pinfunction "1_1") (pintype "passive"))
      (node (ref "D14") (pin "10") (pinfunction "GND_10") (pintype "power_in"))
      (node (ref "R92") (pin "2") (pinfunction "2_2") (pintype "passive"))
    )
    (net (code "78") (name "Net-(D14-VOUTA)") (class "Default")
      (node (ref "D14") (pin "5") (pinfunction "VOUTA_5") (pintype "tri_state"))
      (node (ref "X6") (pin "1") (pinfunction "Left_1") (pintype "passive"))
    )
    (net (code "79") (name "Net-(D14-VOUTB)") (class "Default")
      (node (ref "D14") (pin "6") (pinfunction "VOUTB_6") (pintype "tri_state"))
      (node (ref "X6") (pin "3") (pinfunction "Rigth_3") (pintype "passive"))
    )
    (net (code "80") (name "Net-(D14-VREFA)") (class "Default")
      (node (ref "C219") (pin "2") (pinfunction "2_2") (pintype "passive"))
      (node (ref "D14") (pin "3") (pinfunction "VREFB_3") (pintype "input"))
      (node (ref "D14") (pin "4") (pinfunction "VREFA_4") (pintype "input"))
      (node (ref "R91") (pin "1") (pinfunction "1_1") (pintype "passive"))
      (node (ref "R92") (pin "1") (pinfunction "1_1") (pintype "passive"))
    )
    (net (code "81") (name "Net-(D15A-BYPASS)") (class "Default")
      (node (ref "C245") (pin "2") (pinfunction "2_2") (pintype "passive"))
      (node (ref "D15") (pin "9") (pinfunction "BYPASS_9") (pintype "passive"))
    )
    (net (code "82") (name "Net-(D15A-CP)") (class "Default")
      (node (ref "C247") (pin "2") (pinfunction "2_2") (pintype "passive"))
      (node (ref "D15") (pin "4") (pinfunction "CP_4") (pintype "output"))
      (node (ref "D15") (pin "8") (pinfunction "LF_8") (pintype "input"))
      (node (ref "R107") (pin "1") (pinfunction "1_1") (pintype "passive"))
    )
    (net (code "83") (name "Net-(D15A-CPRSET)") (class "Default")
      (node (ref "D15") (pin "46") (pinfunction "CPRSET_46") (pintype "input"))
      (node (ref "R106") (pin "1") (pinfunction "1_1") (pintype "passive"))
    )
    (net (code "84") (name "Net-(D15A-RSET)") (class "Default")
      (node (ref "D15") (pin "44") (pinfunction "RSET_44") (pintype "input"))
      (node (ref "R105") (pin "1") (pinfunction "1_1") (pintype "passive"))
    )
    (net (code "85") (name "Net-(D15A-~{CLK})") (class "Default")
      (node (ref "C236") (pin "2") (pinfunction "2_2") (pintype "passive"))
      (node (ref "D15") (pin "12") (pinfunction "~{CLK}_12") (pintype "input"))
    )
    (net (code "86") (name "Net-(D15B-VCP)") (class "Default")
      (node (ref "C243") (pin "2") (pinfunction "2_2") (pintype "passive"))
      (node (ref "C244") (pin "2") (pinfunction "2_2") (pintype "passive"))
      (node (ref "D15") (pin "3") (pinfunction "VCP_3") (pintype "power_in"))
      (node (ref "L16") (pin "1") (pinfunction "1_1") (pintype "passive"))
    )
    (net (code "87") (name "Net-(R85-Pad2)") (class "Default")
      (node (ref "R85") (pin "2") (pinfunction "2_2") (pintype "passive"))
      (node (ref "T1") (pin "3") (pinfunction "3_3") (pintype "passive"))
    )
    (net (code "88") (name "Net-(R89-Pad2)") (class "Default")
      (node (ref "R89") (pin "2") (pinfunction "2_2") (pintype "passive"))
      (node (ref "T1") (pin "1") (pinfunction "1_1") (pintype "passive"))
    )
    (net (code "89") (name "Net-(R96-Pad2)") (class "Default")
      (node (ref "R96") (pin "2") (pinfunction "2_2") (pintype "passive"))
      (node (ref "T2") (pin "3") (pinfunction "3_3") (pintype "passive"))
    )
    (net (code "90") (name "Net-(R100-Pad2)") (class "Default")
      (node (ref "R100") (pin "2") (pinfunction "2_2") (pintype "passive"))
      (node (ref "T2") (pin "1") (pinfunction "1_1") (pintype "passive"))
    )
    (net (code "91") (name "Net-(VG2-EN)") (class "Default")
      (node (ref "R102") (pin "2") (pinfunction "2_2") (pintype "passive"))
      (node (ref "VG2") (pin "1") (pinfunction "EN_1") (pintype "passive"))
    )
    (net (code "92") (name "unconnected-(D13A-D0B_(LSB)FD2--Pad58)") (class "Default")
      (node (ref "D13") (pin "58") (pinfunction "D0B_(LSB)FD2-_58") (pintype "tri_state"))
    )
    (net (code "93") (name "unconnected-(D13A-D1BFD2+-Pad59)") (class "Default")
      (node (ref "D13") (pin "59") (pinfunction "D1BFD2+_59") (pintype "tri_state"))
    )
    (net (code "94") (name "unconnected-(D13A-D2BFD3--Pad60)") (class "Default")
      (node (ref "D13") (pin "60") (pinfunction "D2BFD3-_60") (pintype "tri_state"))
    )
    (net (code "95") (name "unconnected-(D13A-D3BFD3+-Pad61)") (class "Default")
      (node (ref "D13") (pin "61") (pinfunction "D3BFD3+_61") (pintype "tri_state"))
    )
    (net (code "96") (name "unconnected-(D13A-FD0BFD0--Pad53)") (class "Default")
      (node (ref "D13") (pin "53") (pinfunction "FD0BFD0-_53") (pintype "output"))
    )
    (net (code "97") (name "unconnected-(D13A-FD1BFD0+-Pad54)") (class "Default")
      (node (ref "D13") (pin "54") (pinfunction "FD1BFD0+_54") (pintype "output"))
    )
    (net (code "98") (name "unconnected-(D13A-FD2BFD1--Pad55)") (class "Default")
      (node (ref "D13") (pin "55") (pinfunction "FD2BFD1-_55") (pintype "output"))
    )
    (net (code "99") (name "unconnected-(D13A-FD3BFD1+-Pad56)") (class "Default")
      (node (ref "D13") (pin "56") (pinfunction "FD3BFD1+_56") (pintype "output"))
    )
    (net (code "100") (name "unconnected-(D13B-SMI_SCLK{slash}PDWN-Pad34)") (class "Default")
      (node (ref "D13") (pin "34") (pinfunction "SMI_SCLK/PDWN_34") (pintype "bidirectional"))
    )
    (net (code "101") (name "unconnected-(D13B-SMI_SDFS-Pad35)") (class "Default")
      (node (ref "D13") (pin "35") (pinfunction "SMI_SDFS_35") (pintype "output"))
    )
    (net (code "102") (name "unconnected-(D13B-SMI_SDO{slash}OEB-Pad33)") (class "Default")
      (node (ref "D13") (pin "33") (pinfunction "SMI_SDO/OEB_33") (pintype "bidirectional"))
    )
    (net (code "103") (name "unconnected-(D15A-CLK-Pad11)") (class "Default")
      (node (ref "D15") (pin "11") (pinfunction "CLK_11") (pintype "input"))
    )
    (net (code "104") (name "unconnected-(D15A-LD-Pad2)") (class "Default")
      (node (ref "D15") (pin "2") (pinfunction "LD_2") (pintype "output"))
    )
    (net (code "105") (name "unconnected-(D15A-OUT0-Pad42)") (class "Default")
      (node (ref "D15") (pin "42") (pinfunction "OUT0_42") (pintype "output"))
    )
    (net (code "106") (name "unconnected-(D15A-OUT1-Pad39)") (class "Default")
      (node (ref "D15") (pin "39") (pinfunction "OUT1_39") (pintype "output"))
    )
    (net (code "107") (name "unconnected-(D15A-OUT2-Pad19)") (class "Default")
      (node (ref "D15") (pin "19") (pinfunction "OUT2_19") (pintype "output"))
    )
    (net (code "108") (name "unconnected-(D15A-OUT3-Pad22)") (class "Default")
      (node (ref "D15") (pin "22") (pinfunction "OUT3_22") (pintype "output"))
    )
    (net (code "109") (name "unconnected-(D15A-OUT5(OUT5A)-Pad33)") (class "Default")
      (node (ref "D15") (pin "33") (pinfunction "OUT5(OUT5A)_33") (pintype "output"))
    )
    (net (code "110") (name "unconnected-(D15A-OUT6(OUT6A)-Pad26)") (class "Default")
      (node (ref "D15") (pin "26") (pinfunction "OUT6(OUT6A)_26") (pintype "output"))
    )
    (net (code "111") (name "unconnected-(D15A-OUT7(OUT7A)-Pad28)") (class "Default")
      (node (ref "D15") (pin "28") (pinfunction "OUT7(OUT7A)_28") (pintype "output"))
    )
    (net (code "112") (name "unconnected-(D15A-~{OUT0}-Pad41)") (class "Default")
      (node (ref "D15") (pin "41") (pinfunction "~{OUT0}_41") (pintype "output"))
    )
    (net (code "113") (name "unconnected-(D15A-~{OUT1}-Pad38)") (class "Default")
      (node (ref "D15") (pin "38") (pinfunction "~{OUT1}_38") (pintype "output"))
    )
    (net (code "114") (name "unconnected-(D15A-~{OUT2}-Pad20)") (class "Default")
      (node (ref "D15") (pin "20") (pinfunction "~{OUT2}_20") (pintype "output"))
    )
    (net (code "115") (name "unconnected-(D15A-~{OUT3}-Pad23)") (class "Default")
      (node (ref "D15") (pin "23") (pinfunction "~{OUT3}_23") (pintype "output"))
    )
    (net (code "116") (name "unconnected-(D15A-~{OUT5}(OUT5B)-Pad32)") (class "Default")
      (node (ref "D15") (pin "32") (pinfunction "~{OUT5}(OUT5B)_32") (pintype "output"))
    )
    (net (code "117") (name "unconnected-(D15A-~{OUT6}(OUT6B)-Pad27)") (class "Default")
      (node (ref "D15") (pin "27") (pinfunction "~{OUT6}(OUT6B)_27") (pintype "output"))
    )
    (net (code "118") (name "unconnected-(D15A-~{OUT7}(OUT7B)-Pad29)") (class "Default")
      (node (ref "D15") (pin "29") (pinfunction "~{OUT7}(OUT7B)_29") (pintype "output"))
    )
    (net (code "119") (name "unconnected-(D15A-~{PD}-Pad18)") (class "Default")
      (node (ref "D15") (pin "18") (pinfunction "~{PD}_18") (pintype "input"))
    )
    (net (code "120") (name "unconnected-(D15A-~{RESET}-Pad17)") (class "Default")
      (node (ref "D15") (pin "17") (pinfunction "~{RESET}_17") (pintype "input"))
    )
    (net (code "121") (name "unconnected-(D15A-~{SYNC}-Pad7)") (class "Default")
      (node (ref "D15") (pin "7") (pinfunction "~{SYNC}_7") (pintype "input"))
    )
    (net (code "122") (name "unconnected-(T1-Pad5)") (class "Default")
      (node (ref "T1") (pin "5") (pinfunction "5_5") (pintype "passive"))
    )
    (net (code "123") (name "unconnected-(T2-Pad5)") (class "Default")
      (node (ref "T2") (pin "5") (pinfunction "5_5") (pintype "passive"))
    )
  )
)
